# GBWandR1-FIXED.net
KiCad netlist of a schematic drawn in EAGLE
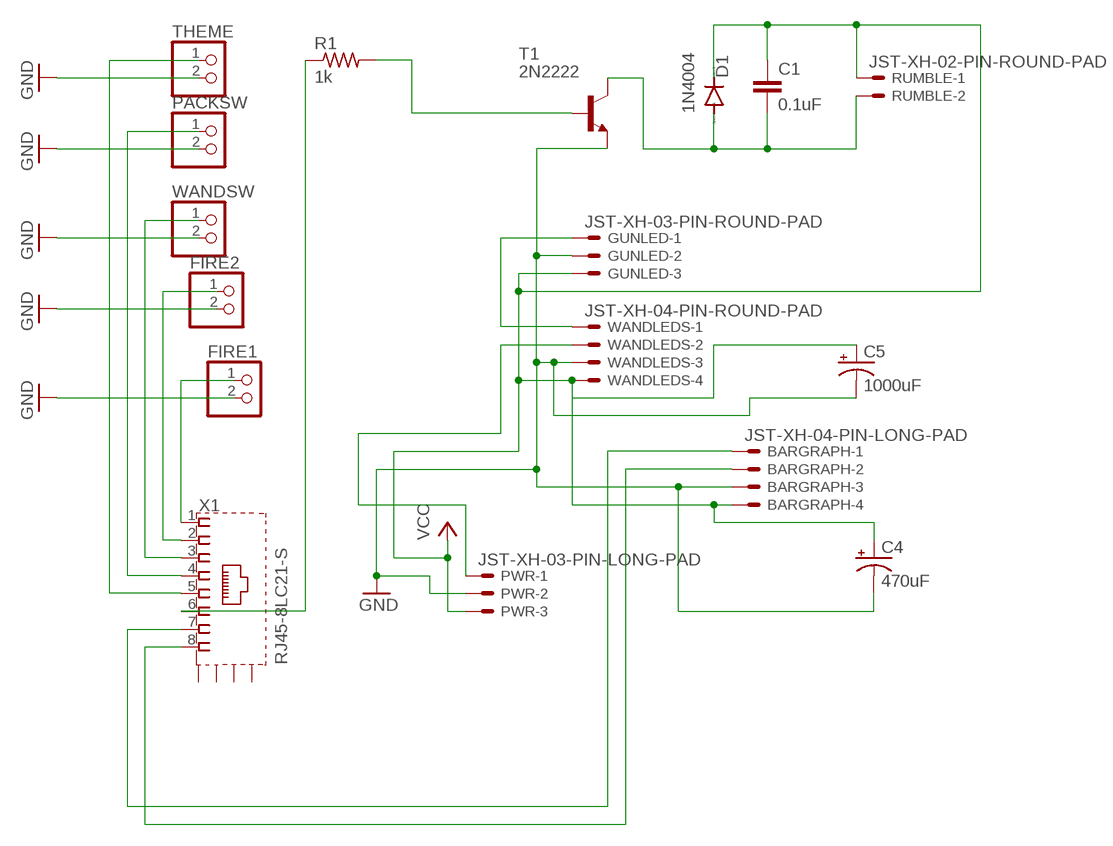
[diagram p0: schematic, sheet 1]

(export (version "E")
  (design (tool "Eeschema 10.0.6"))
  (components
    (comp (ref "BARGRAPH")
      (value "JST-XH-04-PIN-LONG-PAD")
      (footprint "eagle-import:JST-XH-04-PACKAGE-LONG-PAD")
      (libsource (lib "eagle-import") (part "JST-XH-04-PIN-LONG-PAD"))
    )
    (comp (ref "C1")
      (value "0.1uF")
      (footprint "eagle-import:C050-024X044")
      (libsource (lib "eagle-import") (part "C-EU050-024X044"))
    )
    (comp (ref "C4")
      (value "470uF")
      (footprint "eagle-import:E3,5-8")
      (libsource (lib "eagle-import") (part "CPOL-USE3.5-8"))
    )
    (comp (ref "C5")
      (value "1000uF")
      (footprint "eagle-import:E3,5-8")
      (libsource (lib "eagle-import") (part "CPOL-USE3.5-8"))
    )
    (comp (ref "D1")
      (value "1N4004")
      (footprint "eagle-import:DO41-10")
      (libsource (lib "eagle-import") (part "1N4004"))
    )
    (comp (ref "FIRE1")
      (value "PINHD-1X2")
      (footprint "eagle-import:1X02")
      (libsource (lib "eagle-import") (part "PINHD-1X2"))
    )
    (comp (ref "FIRE2")
      (value "PINHD-1X2")
      (footprint "eagle-import:1X02")
      (libsource (lib "eagle-import") (part "PINHD-1X2"))
    )
    (comp (ref "GUNLED")
      (value "JST-XH-03-PIN-ROUND-PAD")
      (footprint "eagle-import:JST-XH-03-PACKAGE-ROUND-PAD")
      (libsource (lib "eagle-import") (part "JST-XH-03-PIN-ROUND-PAD"))
    )
    (comp (ref "PACKSW")
      (value "PINHD-1X2")
      (footprint "eagle-import:1X02")
      (libsource (lib "eagle-import") (part "PINHD-1X2"))
    )
    (comp (ref "PWR")
      (value "JST-XH-03-PIN-LONG-PAD")
      (footprint "eagle-import:JST-XH-03-PACKAGE-LONG-PAD")
      (libsource (lib "eagle-import") (part "JST-XH-03-PIN-LONG-PAD"))
    )
    (comp (ref "R1")
      (value "1k")
      (footprint "eagle-import:0207_9")
      (libsource (lib "eagle-import") (part "R-US_0207/9"))
    )
    (comp (ref "RUMBLE")
      (value "JST-XH-02-PIN-ROUND-PAD")
      (footprint "eagle-import:JST-XH-02-PACKAGE-ROUND-PAD")
      (libsource (lib "eagle-import") (part "JST-XH-02-PIN-ROUND-PAD"))
    )
    (comp (ref "T1")
      (value "2N2222")
      (footprint "eagle-import:TO92-EBC-OVAL")
      (libsource (lib "eagle-import") (part "2N2222"))
    )
    (comp (ref "THEME")
      (value "PINHD-1X2")
      (footprint "eagle-import:1X02")
      (libsource (lib "eagle-import") (part "PINHD-1X2"))
    )
    (comp (ref "WANDLEDS")
      (value "JST-XH-04-PIN-ROUND-PAD")
      (footprint "eagle-import:JST-XH-04-PACKAGE-ROUND-PAD")
      (libsource (lib "eagle-import") (part "JST-XH-04-PIN-ROUND-PAD"))
    )
    (comp (ref "WANDSW")
      (value "PINHD-1X2")
      (footprint "eagle-import:1X02")
      (libsource (lib "eagle-import") (part "PINHD-1X2"))
    )
    (comp (ref "X1")
      (value "RJ45-8LC21-S")
      (footprint "eagle-import:RJ45-SHIELD1")
      (libsource (lib "eagle-import") (part "RJ4521-S-8LC"))
    )
  )
  (nets
    (net (code "1") (name "GND") (class "Default")
      (node (ref "BARGRAPH") (pin "3") (pinfunction "S_3") (pintype "passive"))
      (node (ref "C4") (pin "-") (pinfunction "-_-") (pintype "passive"))
      (node (ref "C5") (pin "-") (pinfunction "-_-") (pintype "passive"))
      (node (ref "FIRE1") (pin "2") (pinfunction "2_2") (pintype "passive"))
      (node (ref "FIRE2") (pin "2") (pinfunction "2_2") (pintype "passive"))
      (node (ref "GUNLED") (pin "2") (pinfunction "S_2") (pintype "passive"))
      (node (ref "PACKSW") (pin "2") (pinfunction "2_2") (pintype "passive"))
      (node (ref "PWR") (pin "2") (pinfunction "S_2") (pintype "passive"))
      (node (ref "T1") (pin "E") (pinfunction "E_E") (pintype "passive"))
      (node (ref "THEME") (pin "2") (pinfunction "2_2") (pintype "passive"))
      (node (ref "WANDLEDS") (pin "3") (pinfunction "S_3") (pintype "passive"))
      (node (ref "WANDSW") (pin "2") (pinfunction "2_2") (pintype "passive"))
    )
    (net (code "2") (name "Net-(BARGRAPHA-S)") (class "Default")
      (node (ref "BARGRAPH") (pin "1") (pinfunction "S_1") (pintype "passive"))
      (node (ref "X1") (pin "7") (pinfunction "7_7") (pintype "passive"))
    )
    (net (code "3") (name "Net-(BARGRAPHB-S)") (class "Default")
      (node (ref "BARGRAPH") (pin "2") (pinfunction "S_2") (pintype "passive"))
      (node (ref "X1") (pin "8") (pinfunction "8_8") (pintype "passive"))
    )
    (net (code "4") (name "Net-(FIRE1-Pad1)") (class "Default")
      (node (ref "FIRE1") (pin "1") (pinfunction "1_1") (pintype "passive"))
      (node (ref "X1") (pin "1") (pinfunction "1_1") (pintype "passive"))
    )
    (net (code "5") (name "Net-(FIRE2-Pad1)") (class "Default")
      (node (ref "FIRE2") (pin "1") (pinfunction "1_1") (pintype "passive"))
      (node (ref "X1") (pin "2") (pinfunction "2_2") (pintype "passive"))
    )
    (net (code "6") (name "Net-(GUNLEDA-S)") (class "Default")
      (node (ref "GUNLED") (pin "1") (pinfunction "S_1") (pintype "passive"))
      (node (ref "WANDLEDS") (pin "1") (pinfunction "S_1") (pintype "passive"))
    )
    (net (code "7") (name "Net-(PACKSW-Pad1)") (class "Default")
      (node (ref "PACKSW") (pin "1") (pinfunction "1_1") (pintype "passive"))
      (node (ref "X1") (pin "4") (pinfunction "4_4") (pintype "passive"))
    )
    (net (code "8") (name "Net-(PWRA-S)") (class "Default")
      (node (ref "PWR") (pin "1") (pinfunction "S_1") (pintype "passive"))
      (node (ref "WANDLEDS") (pin "2") (pinfunction "S_2") (pintype "passive"))
    )
    (net (code "9") (name "Net-(R1-Pad1)") (class "Default")
      (node (ref "R1") (pin "1") (pinfunction "1_1") (pintype "passive"))
      (node (ref "X1") (pin "6") (pinfunction "6_6") (pintype "passive"))
    )
    (net (code "10") (name "Net-(R1-Pad2)") (class "Default")
      (node (ref "R1") (pin "2") (pinfunction "2_2") (pintype "passive"))
      (node (ref "T1") (pin "B") (pinfunction "B_B") (pintype "passive"))
    )
    (net (code "11") (name "Net-(RUMBLEB-S)") (class "Default")
      (node (ref "C1") (pin "2") (pinfunction "2_2") (pintype "passive"))
      (node (ref "D1") (pin "A") (pinfunction "A_A") (pintype "passive"))
      (node (ref "RUMBLE") (pin "2") (pinfunction "S_2") (pintype "passive"))
      (node (ref "T1") (pin "C") (pinfunction "C_C") (pintype "passive"))
    )
    (net (code "12") (name "Net-(THEME-Pad1)") (class "Default")
      (node (ref "THEME") (pin "1") (pinfunction "1_1") (pintype "passive"))
      (node (ref "X1") (pin "5") (pinfunction "5_5") (pintype "passive"))
    )
    (net (code "13") (name "Net-(WANDSW-Pad1)") (class "Default")
      (node (ref "WANDSW") (pin "1") (pinfunction "1_1") (pintype "passive"))
      (node (ref "X1") (pin "3") (pinfunction "3_3") (pintype "passive"))
    )
    (net (code "14") (name "VCC") (class "Default")
      (node (ref "BARGRAPH") (pin "4") (pinfunction "S_4") (pintype "passive"))
      (node (ref "C1") (pin "1") (pinfunction "1_1") (pintype "passive"))
      (node (ref "C4") (pin "+") (pinfunction "+_+") (pintype "passive"))
      (node (ref "C5") (pin "+") (pinfunction "+_+") (pintype "passive"))
      (node (ref "D1") (pin "C") (pinfunction "C_C") (pintype "passive"))
      (node (ref "GUNLED") (pin "3") (pinfunction "S_3") (pintype "passive"))
      (node (ref "PWR") (pin "3") (pinfunction "S_3") (pintype "passive"))
      (node (ref "RUMBLE") (pin "1") (pinfunction "S_1") (pintype "passive"))
      (node (ref "WANDLEDS") (pin "4") (pinfunction "S_4") (pintype "passive"))
    )
    (net (code "15") (name "unconnected-(X1-S-PadS1)") (class "Default")
      (node (ref "X1") (pin "S1") (pinfunction "S_S1") (pintype "passive"))
    )
    (net (code "16") (name "unconnected-(X1-S-PadS2)") (class "Default")
      (node (ref "X1") (pin "S2") (pinfunction "S_S2") (pintype "passive"))
    )
    (net (code "17") (name "unconnected-(X1-S-PadS3)") (class "Default")
      (node (ref "X1") (pin "S3") (pinfunction "S_S3") (pintype "passive"))
    )
    (net (code "18") (name "unconnected-(X1-S-PadS4)") (class "Default")
      (node (ref "X1") (pin "S4") (pinfunction "S_S4") (pintype "passive"))
    )
  )
)
